# schematic_v2.net
KiCad netlist of a schematic drawn in EAGLE
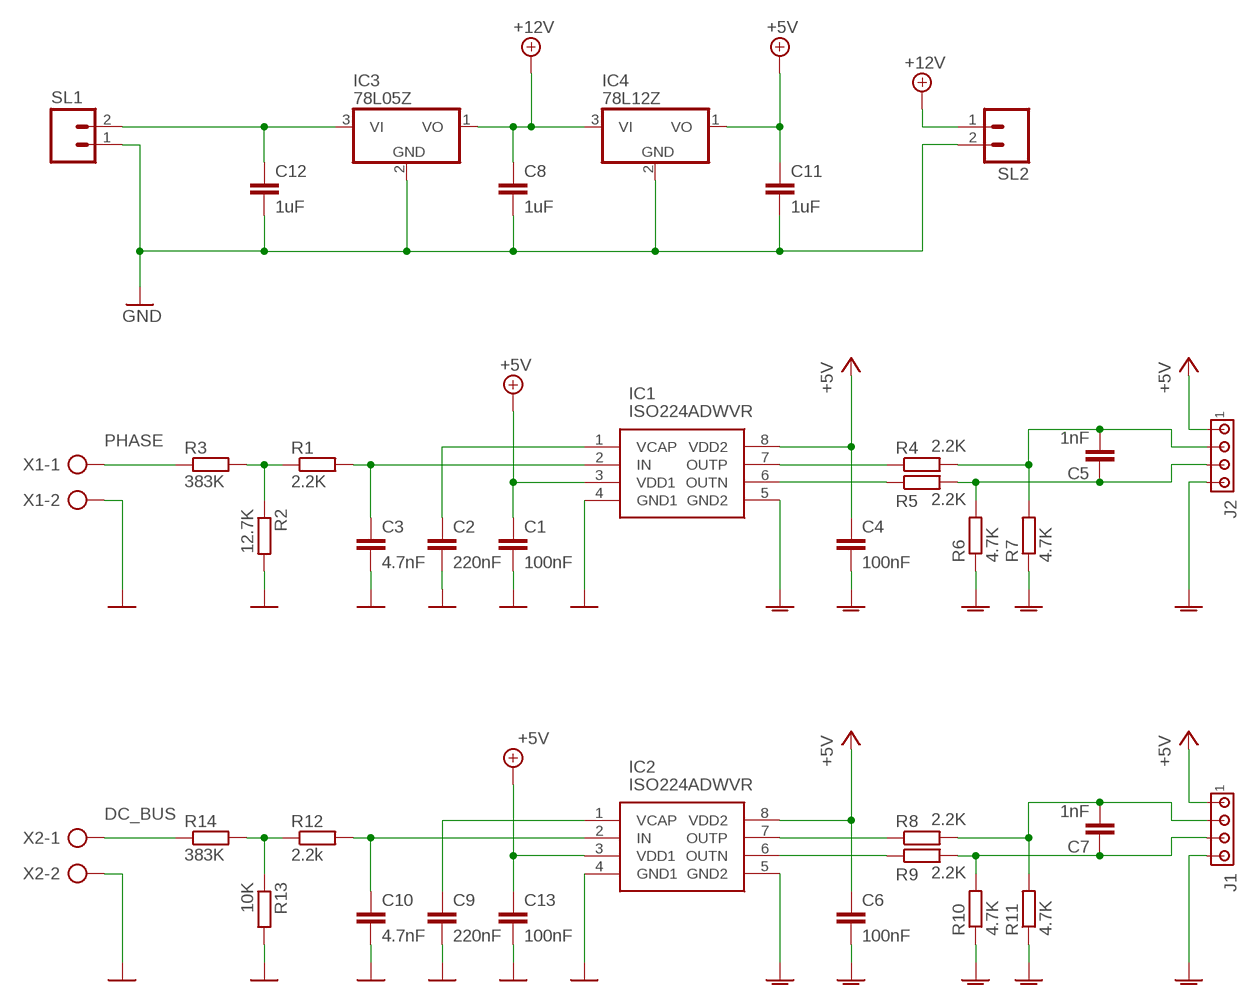
[diagram p0: schematic, sheet 1]

(export (version "E")
  (design (tool "Eeschema 10.0.6"))
  (components
    (comp (ref "C1")
      (value "100nF")
      (footprint "eagle-import:C0805")
      (libsource (lib "eagle-import") (part "C-EUC0805"))
    )
    (comp (ref "C2")
      (value "220nF")
      (footprint "eagle-import:C0805")
      (libsource (lib "eagle-import") (part "C-EUC0805"))
    )
    (comp (ref "C3")
      (value "4.7nF")
      (footprint "eagle-import:C0805")
      (libsource (lib "eagle-import") (part "C-EUC0805"))
    )
    (comp (ref "C4")
      (value "100nF")
      (footprint "eagle-import:C0805")
      (libsource (lib "eagle-import") (part "C-EUC0805"))
    )
    (comp (ref "C5")
      (value "1nF")
      (footprint "eagle-import:C0805")
      (libsource (lib "eagle-import") (part "C-EUC0805"))
    )
    (comp (ref "C6")
      (value "100nF")
      (footprint "eagle-import:C0805")
      (libsource (lib "eagle-import") (part "C-EUC0805"))
    )
    (comp (ref "C7")
      (value "1nF")
      (footprint "eagle-import:C0805")
      (libsource (lib "eagle-import") (part "C-EUC0805"))
    )
    (comp (ref "C8")
      (value "1uF")
      (footprint "eagle-import:C0805")
      (libsource (lib "eagle-import") (part "C-EUC0805"))
    )
    (comp (ref "C9")
      (value "220nF")
      (footprint "eagle-import:C0805")
      (libsource (lib "eagle-import") (part "C-EUC0805"))
    )
    (comp (ref "C10")
      (value "4.7nF")
      (footprint "eagle-import:C0805")
      (libsource (lib "eagle-import") (part "C-EUC0805"))
    )
    (comp (ref "C11")
      (value "1uF")
      (footprint "eagle-import:C0805")
      (libsource (lib "eagle-import") (part "C-EUC0805"))
    )
    (comp (ref "C12")
      (value "1uF")
      (footprint "eagle-import:C0805")
      (libsource (lib "eagle-import") (part "C-EUC0805"))
    )
    (comp (ref "C13")
      (value "100nF")
      (footprint "eagle-import:C0805")
      (libsource (lib "eagle-import") (part "C-EUC0805"))
    )
    (comp (ref "IC1")
      (value "ISO224ADWVR")
      (footprint "eagle-import:SOIC127P1150X280-8N")
      (fields (field (name "MOUSER_PART_NUMBER") "595-ISO224ADWVR"))
      (libsource (lib "eagle-import") (part "ISO224ADWVR"))
    )
    (comp (ref "IC2")
      (value "ISO224ADWVR")
      (footprint "eagle-import:SOIC127P1150X280-8N")
      (fields (field (name "MOUSER_PART_NUMBER") "595-ISO224ADWVR"))
      (libsource (lib "eagle-import") (part "ISO224ADWVR"))
    )
    (comp (ref "IC3")
      (value "78L05Z")
      (footprint "eagle-import:TO92")
      (libsource (lib "eagle-import") (part "78ZL05"))
    )
    (comp (ref "IC4")
      (value "78L12Z")
      (footprint "eagle-import:TO92")
      (libsource (lib "eagle-import") (part "78ZL12"))
    )
    (comp (ref "J1")
      (value "MTA04-100")
      (footprint "eagle-import:10X04MTA")
      (libsource (lib "eagle-import") (part "MTA04-100"))
    )
    (comp (ref "J2")
      (value "MTA04-100")
      (footprint "eagle-import:10X04MTA")
      (libsource (lib "eagle-import") (part "MTA04-100"))
    )
    (comp (ref "R1")
      (value "2.2K")
      (footprint "eagle-import:R0805")
      (libsource (lib "eagle-import") (part "R-EU_R0805"))
    )
    (comp (ref "R2")
      (value "12.7K")
      (footprint "eagle-import:0207_10")
      (libsource (lib "eagle-import") (part "R-EU_0207/10"))
    )
    (comp (ref "R3")
      (value "383K")
      (footprint "eagle-import:0207_10")
      (libsource (lib "eagle-import") (part "R-EU_0207/10"))
    )
    (comp (ref "R4")
      (value "2.2K")
      (footprint "eagle-import:R0805")
      (libsource (lib "eagle-import") (part "R-EU_R0805"))
    )
    (comp (ref "R5")
      (value "2.2K")
      (footprint "eagle-import:R0805")
      (libsource (lib "eagle-import") (part "R-EU_R0805"))
    )
    (comp (ref "R6")
      (value "4.7K")
      (footprint "eagle-import:R0805")
      (libsource (lib "eagle-import") (part "R-EU_R0805"))
    )
    (comp (ref "R7")
      (value "4.7K")
      (footprint "eagle-import:R0805")
      (libsource (lib "eagle-import") (part "R-EU_R0805"))
    )
    (comp (ref "R8")
      (value "2.2K")
      (footprint "eagle-import:R0805")
      (libsource (lib "eagle-import") (part "R-EU_R0805"))
    )
    (comp (ref "R9")
      (value "2.2K")
      (footprint "eagle-import:R0805")
      (libsource (lib "eagle-import") (part "R-EU_R0805"))
    )
    (comp (ref "R10")
      (value "4.7K")
      (footprint "eagle-import:R0805")
      (libsource (lib "eagle-import") (part "R-EU_R0805"))
    )
    (comp (ref "R11")
      (value "4.7K")
      (footprint "eagle-import:R0805")
      (libsource (lib "eagle-import") (part "R-EU_R0805"))
    )
    (comp (ref "R12")
      (value "2.2k")
      (footprint "eagle-import:R0805")
      (libsource (lib "eagle-import") (part "R-EU_R0805"))
    )
    (comp (ref "R13")
      (value "10K")
      (footprint "eagle-import:0207_10")
      (libsource (lib "eagle-import") (part "R-EU_0207/10"))
    )
    (comp (ref "R14")
      (value "383K")
      (footprint "eagle-import:0207_10")
      (libsource (lib "eagle-import") (part "R-EU_0207/10"))
    )
    (comp (ref "SL1")
      (value "M02")
      (footprint "eagle-import:02P")
      (libsource (lib "eagle-import") (part "M02"))
    )
    (comp (ref "SL2")
      (value "M02")
      (footprint "eagle-import:02P")
      (libsource (lib "eagle-import") (part "M02"))
    )
    (comp (ref "X1")
      (value "AK500/2")
      (footprint "eagle-import:AK500_2")
      (libsource (lib "eagle-import") (part "AK500/2"))
    )
    (comp (ref "X2")
      (value "AK500/2")
      (footprint "eagle-import:AK500_2")
      (libsource (lib "eagle-import") (part "AK500/2"))
    )
  )
  (nets
    (net (code "1") (name "+5V") (class "Default")
      (node (ref "C1") (pin "1") (pinfunction "1_1") (pintype "passive"))
      (node (ref "C11") (pin "1") (pinfunction "1_1") (pintype "passive"))
      (node (ref "C13") (pin "1") (pinfunction "1_1") (pintype "passive"))
      (node (ref "C4") (pin "1") (pinfunction "1_1") (pintype "passive"))
      (node (ref "C6") (pin "1") (pinfunction "1_1") (pintype "passive"))
      (node (ref "IC1") (pin "3") (pinfunction "VDD1_3") (pintype "bidirectional"))
      (node (ref "IC1") (pin "8") (pinfunction "VDD2_8") (pintype "bidirectional"))
      (node (ref "IC2") (pin "3") (pinfunction "VDD1_3") (pintype "bidirectional"))
      (node (ref "IC2") (pin "8") (pinfunction "VDD2_8") (pintype "bidirectional"))
      (node (ref "IC4") (pin "1") (pinfunction "VO_1") (pintype "passive"))
      (node (ref "J1") (pin "1") (pinfunction "1_1") (pintype "passive"))
      (node (ref "J2") (pin "1") (pinfunction "1_1") (pintype "passive"))
    )
    (net (code "2") (name "+12V") (class "Default")
      (node (ref "C8") (pin "1") (pinfunction "1_1") (pintype "passive"))
      (node (ref "IC3") (pin "1") (pinfunction "VO_1") (pintype "passive"))
      (node (ref "IC4") (pin "3") (pinfunction "VI_3") (pintype "input"))
      (node (ref "SL2") (pin "1") (pinfunction "1_1") (pintype "passive"))
    )
    (net (code "3") (name "/DC_BUS") (class "Default")
      (node (ref "R14") (pin "1") (pinfunction "1_1") (pintype "passive"))
      (node (ref "X2") (pin "1") (pinfunction "KL_1") (pintype "passive"))
    )
    (net (code "4") (name "/PHASE") (class "Default")
      (node (ref "R3") (pin "1") (pinfunction "1_1") (pintype "passive"))
      (node (ref "X1") (pin "1") (pinfunction "KL_1") (pintype "passive"))
    )
    (net (code "5") (name "GND") (class "Default")
      (node (ref "C1") (pin "2") (pinfunction "2_2") (pintype "passive"))
      (node (ref "C10") (pin "2") (pinfunction "2_2") (pintype "passive"))
      (node (ref "C11") (pin "2") (pinfunction "2_2") (pintype "passive"))
      (node (ref "C12") (pin "2") (pinfunction "2_2") (pintype "passive"))
      (node (ref "C13") (pin "2") (pinfunction "2_2") (pintype "passive"))
      (node (ref "C2") (pin "2") (pinfunction "2_2") (pintype "passive"))
      (node (ref "C3") (pin "2") (pinfunction "2_2") (pintype "passive"))
      (node (ref "C8") (pin "2") (pinfunction "2_2") (pintype "passive"))
      (node (ref "C9") (pin "2") (pinfunction "2_2") (pintype "passive"))
      (node (ref "IC1") (pin "4") (pinfunction "GND1_4") (pintype "bidirectional"))
      (node (ref "IC2") (pin "4") (pinfunction "GND1_4") (pintype "bidirectional"))
      (node (ref "IC3") (pin "2") (pinfunction "GND_2") (pintype "passive"))
      (node (ref "IC4") (pin "2") (pinfunction "GND_2") (pintype "passive"))
      (node (ref "R13") (pin "2") (pinfunction "2_2") (pintype "passive"))
      (node (ref "R2") (pin "2") (pinfunction "2_2") (pintype "passive"))
      (node (ref "SL1") (pin "1") (pinfunction "1_1") (pintype "passive"))
      (node (ref "SL2") (pin "2") (pinfunction "2_2") (pintype "passive"))
      (node (ref "X1") (pin "2") (pinfunction "KL_2") (pintype "passive"))
      (node (ref "X2") (pin "2") (pinfunction "KL_2") (pintype "passive"))
    )
    (net (code "6") (name "GNDA") (class "Default")
      (node (ref "C4") (pin "2") (pinfunction "2_2") (pintype "passive"))
      (node (ref "C6") (pin "2") (pinfunction "2_2") (pintype "passive"))
      (node (ref "IC1") (pin "5") (pinfunction "GND2_5") (pintype "bidirectional"))
      (node (ref "IC2") (pin "5") (pinfunction "GND2_5") (pintype "bidirectional"))
      (node (ref "J1") (pin "4") (pinfunction "4_4") (pintype "passive"))
      (node (ref "J2") (pin "4") (pinfunction "4_4") (pintype "passive"))
      (node (ref "R10") (pin "1") (pinfunction "1_1") (pintype "passive"))
      (node (ref "R11") (pin "1") (pinfunction "1_1") (pintype "passive"))
      (node (ref "R6") (pin "1") (pinfunction "1_1") (pintype "passive"))
      (node (ref "R7") (pin "1") (pinfunction "1_1") (pintype "passive"))
    )
    (net (code "7") (name "Net-(C5-Pad1)") (class "Default")
      (node (ref "C5") (pin "1") (pinfunction "1_1") (pintype "passive"))
      (node (ref "J2") (pin "3") (pinfunction "3_3") (pintype "passive"))
      (node (ref "R5") (pin "2") (pinfunction "2_2") (pintype "passive"))
      (node (ref "R6") (pin "2") (pinfunction "2_2") (pintype "passive"))
    )
    (net (code "8") (name "Net-(C5-Pad2)") (class "Default")
      (node (ref "C5") (pin "2") (pinfunction "2_2") (pintype "passive"))
      (node (ref "J2") (pin "2") (pinfunction "2_2") (pintype "passive"))
      (node (ref "R4") (pin "2") (pinfunction "2_2") (pintype "passive"))
      (node (ref "R7") (pin "2") (pinfunction "2_2") (pintype "passive"))
    )
    (net (code "9") (name "Net-(C7-Pad1)") (class "Default")
      (node (ref "C7") (pin "1") (pinfunction "1_1") (pintype "passive"))
      (node (ref "J1") (pin "3") (pinfunction "3_3") (pintype "passive"))
      (node (ref "R10") (pin "2") (pinfunction "2_2") (pintype "passive"))
      (node (ref "R9") (pin "2") (pinfunction "2_2") (pintype "passive"))
    )
    (net (code "10") (name "Net-(C7-Pad2)") (class "Default")
      (node (ref "C7") (pin "2") (pinfunction "2_2") (pintype "passive"))
      (node (ref "J1") (pin "2") (pinfunction "2_2") (pintype "passive"))
      (node (ref "R11") (pin "2") (pinfunction "2_2") (pintype "passive"))
      (node (ref "R8") (pin "2") (pinfunction "2_2") (pintype "passive"))
    )
    (net (code "11") (name "Net-(IC1-IN)") (class "Default")
      (node (ref "C3") (pin "1") (pinfunction "1_1") (pintype "passive"))
      (node (ref "IC1") (pin "2") (pinfunction "IN_2") (pintype "bidirectional"))
      (node (ref "R1") (pin "2") (pinfunction "2_2") (pintype "passive"))
    )
    (net (code "12") (name "Net-(IC1-OUTN)") (class "Default")
      (node (ref "IC1") (pin "6") (pinfunction "OUTN_6") (pintype "bidirectional"))
      (node (ref "R5") (pin "1") (pinfunction "1_1") (pintype "passive"))
    )
    (net (code "13") (name "Net-(IC1-OUTP)") (class "Default")
      (node (ref "IC1") (pin "7") (pinfunction "OUTP_7") (pintype "bidirectional"))
      (node (ref "R4") (pin "1") (pinfunction "1_1") (pintype "passive"))
    )
    (net (code "14") (name "Net-(IC1-VCAP)") (class "Default")
      (node (ref "C2") (pin "1") (pinfunction "1_1") (pintype "passive"))
      (node (ref "IC1") (pin "1") (pinfunction "VCAP_1") (pintype "bidirectional"))
    )
    (net (code "15") (name "Net-(IC2-IN)") (class "Default")
      (node (ref "C10") (pin "1") (pinfunction "1_1") (pintype "passive"))
      (node (ref "IC2") (pin "2") (pinfunction "IN_2") (pintype "bidirectional"))
      (node (ref "R12") (pin "2") (pinfunction "2_2") (pintype "passive"))
    )
    (net (code "16") (name "Net-(IC2-OUTN)") (class "Default")
      (node (ref "IC2") (pin "6") (pinfunction "OUTN_6") (pintype "bidirectional"))
      (node (ref "R9") (pin "1") (pinfunction "1_1") (pintype "passive"))
    )
    (net (code "17") (name "Net-(IC2-OUTP)") (class "Default")
      (node (ref "IC2") (pin "7") (pinfunction "OUTP_7") (pintype "bidirectional"))
      (node (ref "R8") (pin "1") (pinfunction "1_1") (pintype "passive"))
    )
    (net (code "18") (name "Net-(IC2-VCAP)") (class "Default")
      (node (ref "C9") (pin "1") (pinfunction "1_1") (pintype "passive"))
      (node (ref "IC2") (pin "1") (pinfunction "VCAP_1") (pintype "bidirectional"))
    )
    (net (code "19") (name "Net-(IC3-VI)") (class "Default")
      (node (ref "C12") (pin "1") (pinfunction "1_1") (pintype "passive"))
      (node (ref "IC3") (pin "3") (pinfunction "VI_3") (pintype "input"))
      (node (ref "SL1") (pin "2") (pinfunction "2_2") (pintype "passive"))
    )
    (net (code "20") (name "Net-(R1-Pad1)") (class "Default")
      (node (ref "R1") (pin "1") (pinfunction "1_1") (pintype "passive"))
      (node (ref "R2") (pin "1") (pinfunction "1_1") (pintype "passive"))
      (node (ref "R3") (pin "2") (pinfunction "2_2") (pintype "passive"))
    )
    (net (code "21") (name "Net-(R12-Pad1)") (class "Default")
      (node (ref "R12") (pin "1") (pinfunction "1_1") (pintype "passive"))
      (node (ref "R13") (pin "1") (pinfunction "1_1") (pintype "passive"))
      (node (ref "R14") (pin "2") (pinfunction "2_2") (pintype "passive"))
    )
  )
)
